# CNEPuckCPURevG.net
KiCad netlist of a schematic drawn in Altium Designer
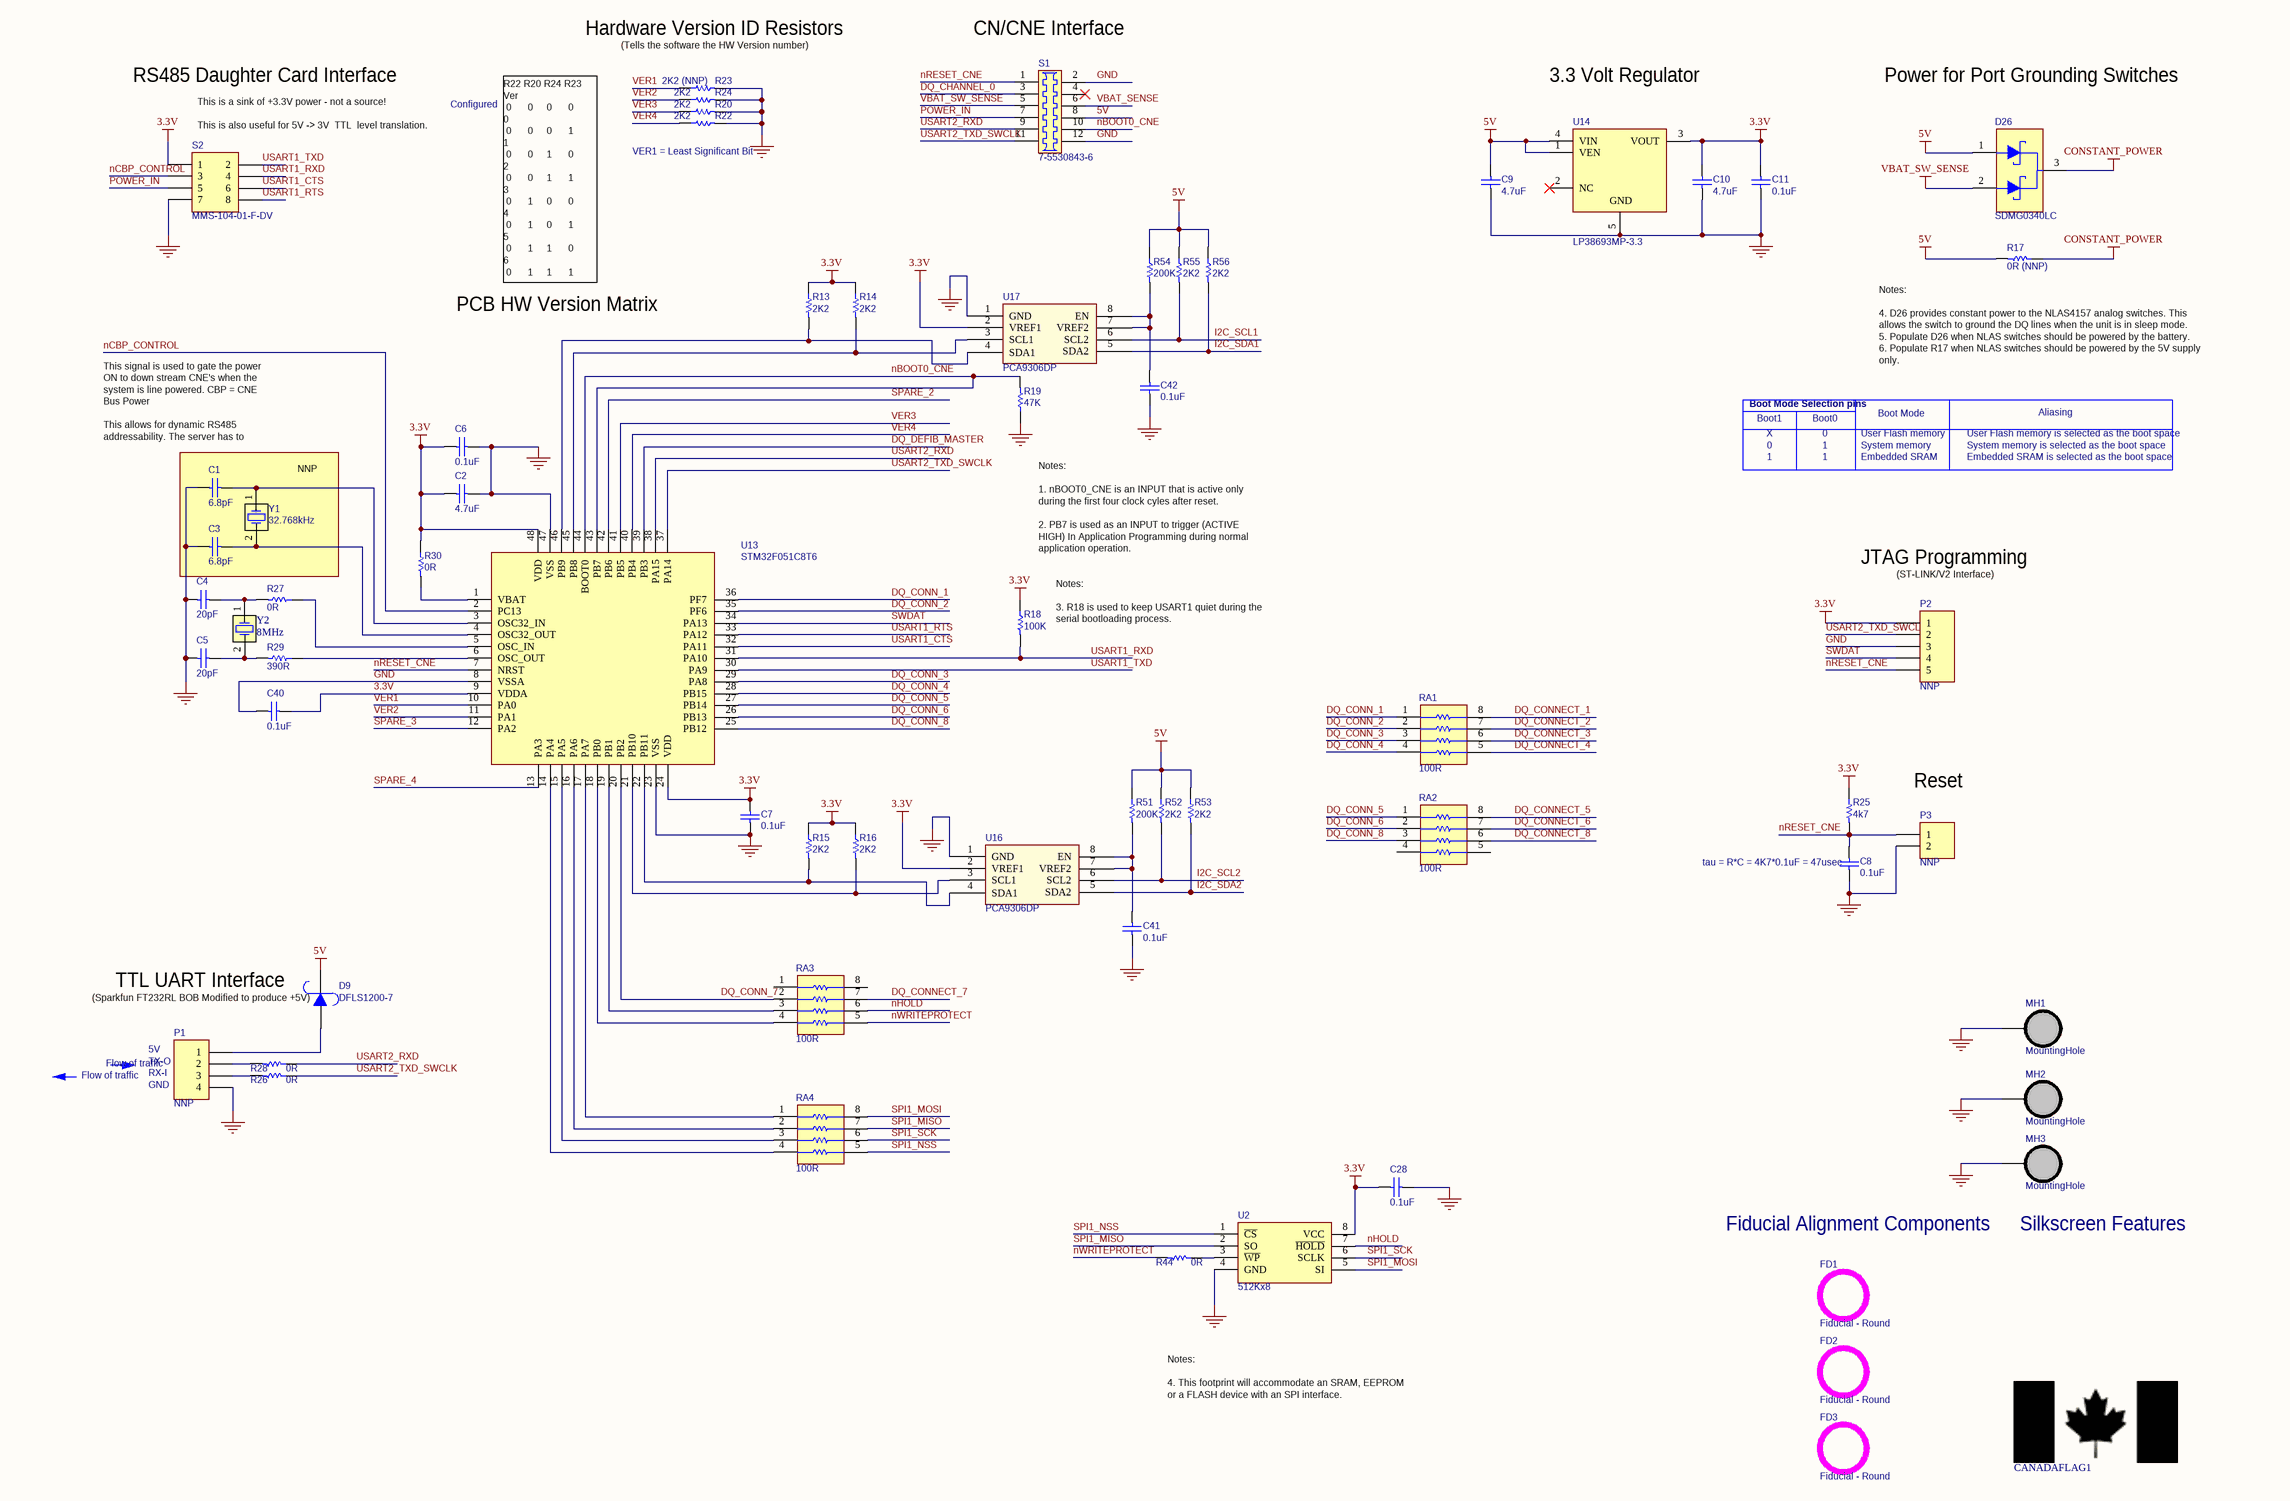
[diagram p0: CNEPuckCPURevG.SchDoc]

(export (version "E")
  (design (tool "Eeschema 10.0.6"))
  (components
    (comp (ref "C1")
      (value "6.8pF")
      (footprint "RC0603")
      (description "CAP CER 6.8PF 50V NP0 0603")
      (fields
        (field (name "MANUFACTURER") "TDK Corporation")
        (field (name "MANUFACTURER PART NUMBER") "C1608C0G1H6R8D")
      )
      (libsource (lib "Swage") (part "C1608C0G1H6R8D"))
    )
    (comp (ref "C2")
      (value "4.7uF")
      (footprint "RC0603")
      (description "CAP CER 4.7UF 10V 10% X5R 0603")
      (fields
        (field (name "MANUFACTURER") "TDK Corporation")
        (field (name "MANUFACTURER PART NUMBER") "C1608X5R1A475K/0.50")
      )
      (libsource (lib "Swage") (part "C1608X5R1A475K/0.50"))
    )
    (comp (ref "C3")
      (value "6.8pF")
      (footprint "RC0603")
      (description "CAP CER 6.8PF 50V NP0 0603")
      (fields
        (field (name "MANUFACTURER") "TDK Corporation")
        (field (name "MANUFACTURER PART NUMBER") "C1608C0G1H6R8D")
      )
      (libsource (lib "Swage") (part "C1608C0G1H6R8D"))
    )
    (comp (ref "C4")
      (value "20pF")
      (footprint "RC0603")
      (description "CAP CER 20PF 50V 5% NPO 0603")
      (fields
        (field (name "MANUFACTURER") "Yageo")
        (field (name "MANUFACTURER PART NUMBER") "CC0603JRNPO9BN200")
      )
      (libsource (lib "Swage") (part "CC0603JRNPO9BN200"))
    )
    (comp (ref "C5")
      (value "20pF")
      (footprint "RC0603")
      (description "CAP CER 20PF 50V 5% NPO 0603")
      (fields
        (field (name "MANUFACTURER") "Yageo")
        (field (name "MANUFACTURER PART NUMBER") "CC0603JRNPO9BN200")
      )
      (libsource (lib "Swage") (part "CC0603JRNPO9BN200"))
    )
    (comp (ref "C6")
      (value "0.1uF")
      (footprint "RC0603")
      (description "CAP CERM .1UF 10% 16V X7R 0603")
      (fields (field (name "TOLERANCE") "±10%") (field (name "MANUFACTURER PART NUMBER") "0603YC104KAT2A"))
      (libsource (lib "Swage") (part "0603YC104KAT2A"))
    )
    (comp (ref "C7")
      (value "0.1uF")
      (footprint "RC0603")
      (description "CAP CERM .1UF 10% 16V X7R 0603")
      (fields (field (name "TOLERANCE") "±10%") (field (name "MANUFACTURER PART NUMBER") "0603YC104KAT2A"))
      (libsource (lib "Swage") (part "0603YC104KAT2A"))
    )
    (comp (ref "C8")
      (value "0.1uF")
      (footprint "RC0603")
      (description "CAP CERM .1UF 10% 16V X7R 0603")
      (fields (field (name "TOLERANCE") "±10%") (field (name "MANUFACTURER PART NUMBER") "0603YC104KAT2A"))
      (libsource (lib "Swage") (part "0603YC104KAT2A"))
    )
    (comp (ref "C9")
      (value "4.7uF")
      (footprint "RC0603")
      (description "CAP CER 4.7UF 10V 10% X5R 0603")
      (fields
        (field (name "MANUFACTURER") "TDK Corporation")
        (field (name "MANUFACTURER PART NUMBER") "C1608X5R1A475K/0.50")
      )
      (libsource (lib "Swage") (part "C1608X5R1A475K/0.50"))
    )
    (comp (ref "C10")
      (value "4.7uF")
      (footprint "RC0603")
      (description "CAP CER 4.7UF 10V 10% X5R 0603")
      (fields
        (field (name "MANUFACTURER") "TDK Corporation")
        (field (name "MANUFACTURER PART NUMBER") "C1608X5R1A475K/0.50")
      )
      (libsource (lib "Swage") (part "C1608X5R1A475K/0.50"))
    )
    (comp (ref "C11")
      (value "0.1uF")
      (footprint "RC0603")
      (description "CAP CERM .1UF 10% 16V X7R 0603")
      (fields (field (name "TOLERANCE") "±10%") (field (name "MANUFACTURER PART NUMBER") "0603YC104KAT2A"))
      (libsource (lib "Swage") (part "0603YC104KAT2A"))
    )
    (comp (ref "C28")
      (value "0.1uF")
      (footprint "RC0603")
      (description "CAP CERM .1UF 10% 16V X7R 0603")
      (fields (field (name "TOLERANCE") "±10%") (field (name "MANUFACTURER PART NUMBER") "0603YC104KAT2A"))
      (libsource (lib "Swage") (part "0603YC104KAT2A"))
    )
    (comp (ref "C40")
      (value "0.1uF")
      (footprint "RC0603")
      (description "CAP CERM .1UF 10% 16V X7R 0603")
      (fields (field (name "TOLERANCE") "±10%") (field (name "MANUFACTURER PART NUMBER") "0603YC104KAT2A"))
      (libsource (lib "Swage") (part "0603YC104KAT2A"))
    )
    (comp (ref "C41")
      (value "0.1uF")
      (footprint "RC0603")
      (description "CAP CERM .1UF 10% 16V X7R 0603")
      (fields (field (name "TOLERANCE") "±10%") (field (name "MANUFACTURER PART NUMBER") "0603YC104KAT2A"))
      (libsource (lib "Swage") (part "0603YC104KAT2A"))
    )
    (comp (ref "C42")
      (value "0.1uF")
      (footprint "RC0603")
      (description "CAP CERM .1UF 10% 16V X7R 0603")
      (fields (field (name "TOLERANCE") "±10%") (field (name "MANUFACTURER PART NUMBER") "0603YC104KAT2A"))
      (libsource (lib "Swage") (part "0603YC104KAT2A"))
    )
    (comp (ref "CANADAFLAG1")
      (value "Canada Flag")
      (footprint "CanadaFlag500x250")
      (libsource (lib "Swage") (part "CanadaFlag"))
    )
    (comp (ref "D9")
      (value "DFLS1200-7")
      (footprint "POWERDI-123")
      (description "DIODE SCHOTTKY 1A 200V PWRDI 123")
      (fields (field (name "MANUFACTURER") "Diodes Inc"))
      (libsource (lib "Swage") (part "DFLS1200-7"))
    )
    (comp (ref "D26")
      (value "SDMG0340LC")
      (footprint "SOT-323")
      (description "DIODE SCHOTTKY 40V 30MA SOT323")
      (fields
        (field (name "MANUFACTURER") "Diodes Inc")
        (field (name "MANUFACTURER PART NUMBER") "SDMG0340LC-7-F")
      )
      (libsource (lib "Swage") (part "SDMG0340LC-7-F"))
    )
    (comp (ref "FD1")
      (value "Fiducial - Round")
      (footprint "FIDUCIAL ROUND SMALL")
      (description "Fiducial Round")
      (libsource (lib "StormaxV13") (part "Fiducial"))
    )
    (comp (ref "FD2")
      (value "Fiducial - Round")
      (footprint "FIDUCIAL ROUND SMALL")
      (description "Fiducial Round")
      (libsource (lib "StormaxV13") (part "Fiducial"))
    )
    (comp (ref "FD3")
      (value "Fiducial - Round")
      (footprint "FIDUCIAL ROUND SMALL")
      (description "Fiducial Round")
      (libsource (lib "StormaxV13") (part "Fiducial"))
    )
    (comp (ref "MH1")
      (value "MountingHole")
      (footprint "MountingHole")
      (description "PCB Mounting Hole, 0.150\" hole, 0.270\" Keepout")
      (libsource (lib "Swage") (part "MountingHole"))
    )
    (comp (ref "MH2")
      (value "MountingHole")
      (footprint "MountingHole")
      (description "PCB Mounting Hole, 0.150\" hole, 0.270\" Keepout")
      (libsource (lib "Swage") (part "MountingHole"))
    )
    (comp (ref "MH3")
      (value "MountingHole")
      (footprint "MountingHole")
      (description "PCB Mounting Hole, 0.150\" hole, 0.270\" Keepout")
      (libsource (lib "Swage") (part "MountingHole"))
    )
    (comp (ref "P1")
      (value "NNP")
      (footprint "HDR1X4")
      (description "Header, 4-Pin")
      (fields
        (field (name "MANUFACTURER") "3M")
        (field (name "MANUFACTURER PART NUMBER") "2340-6111TG")
        (field (name "PUBLISHER") "Altium Limited")
      )
      (libsource (lib "Swage") (part "Header 4"))
    )
    (comp (ref "P2")
      (value "NNP")
      (footprint "HDR1X5")
      (description "Header, 5-Pin")
      (fields
        (field (name "MANUFACTURER PART NUMBER") "2340-6111TG")
        (field (name "MANUFACTURER") "3M")
        (field (name "PUBLISHER") "Altium Limited")
      )
      (libsource (lib "Miscellaneous Connectors") (part "Header 5"))
    )
    (comp (ref "P3")
      (value "NNP")
      (footprint "HDR1X2")
      (description "Header, 2-Pin")
      (fields
        (field (name "MANUFACTURER") "3M")
        (field (name "MANUFACTURER PART NUMBER") "2340-6111TG")
        (field (name "PUBLISHER") "Altium Limited")
      )
      (libsource (lib "Miscellaneous Connectors") (part "Header 2"))
    )
    (comp (ref "R13")
      (value "2K2")
      (footprint "RC0603")
      (description "RES 2.2K OHM 1/10W 5% 0603 SMD")
      (fields
        (field (name "MANUFACTURER") "Panasonic Electronic Components")
        (field (name "MANUFACTURER PART NUMBER") "ERJ-3GEYJ222V")
      )
      (libsource (lib "Swage") (part "ERJ-3GEYJ222V"))
    )
    (comp (ref "R14")
      (value "2K2")
      (footprint "RC0603")
      (description "RES 2.2K OHM 1/10W 5% 0603 SMD")
      (fields
        (field (name "MANUFACTURER") "Panasonic Electronic Components")
        (field (name "MANUFACTURER PART NUMBER") "ERJ-3GEYJ222V")
      )
      (libsource (lib "Swage") (part "ERJ-3GEYJ222V"))
    )
    (comp (ref "R15")
      (value "2K2")
      (footprint "RC0603")
      (description "RES 2.2K OHM 1/10W 5% 0603 SMD")
      (fields
        (field (name "MANUFACTURER") "Panasonic Electronic Components")
        (field (name "MANUFACTURER PART NUMBER") "ERJ-3GEYJ222V")
      )
      (libsource (lib "Swage") (part "ERJ-3GEYJ222V"))
    )
    (comp (ref "R16")
      (value "2K2")
      (footprint "RC0603")
      (description "RES 2.2K OHM 1/10W 5% 0603 SMD")
      (fields
        (field (name "MANUFACTURER") "Panasonic Electronic Components")
        (field (name "MANUFACTURER PART NUMBER") "ERJ-3GEYJ222V")
      )
      (libsource (lib "Swage") (part "ERJ-3GEYJ222V"))
    )
    (comp (ref "R17")
      (value "0R (NNP)")
      (footprint "RC0603")
      (description "RES 0.0 OHM 1/10W 0603 SMD")
      (fields (field (name "TOLERANCE") "Jumper") (field (name "MANUFACTURER") "Panasonic - ECG"))
      (libsource (lib "Swage") (part "ERJ-3GEY0R00V"))
    )
    (comp (ref "R18")
      (value "100K")
      (footprint "RC0603")
      (description "RES 100K OHM 1/10W 5% 0603 SMD")
      (fields
        (field (name "MANUFACTURER") "Panasonic Electronic Components")
        (field (name "MANUFACTURER PART NUMBER") "ERJ-3GEYJ104V")
      )
      (libsource (lib "Swage") (part "ERJ-3GEYJ104V"))
    )
    (comp (ref "R19")
      (value "47K")
      (footprint "RC0603")
      (description "RES 47K OHM 1/10W 5% 0603 SMD")
      (fields (field (name "TOLERANCE") "±5%") (field (name "MANUFACTURER") "Panasonic - ECG"))
      (libsource (lib "Swage") (part "ERJ-3GEYJ473V"))
    )
    (comp (ref "R20")
      (value "2K2")
      (footprint "RC0603")
      (description "RES 2.2K OHM 1/10W 5% 0603 SMD")
      (fields
        (field (name "MANUFACTURER") "Panasonic Electronic Components")
        (field (name "MANUFACTURER PART NUMBER") "ERJ-3GEYJ222V")
      )
      (libsource (lib "Swage") (part "ERJ-3GEYJ222V"))
    )
    (comp (ref "R22")
      (value "2K2")
      (footprint "RC0603")
      (description "RES 2.2K OHM 1/10W 5% 0603 SMD")
      (fields
        (field (name "MANUFACTURER") "Panasonic Electronic Components")
        (field (name "MANUFACTURER PART NUMBER") "ERJ-3GEYJ222V")
      )
      (libsource (lib "Swage") (part "ERJ-3GEYJ222V"))
    )
    (comp (ref "R23")
      (value "2K2 (NNP)")
      (footprint "RC0603")
      (description "RES 2.2K OHM 1/10W 5% 0603 SMD")
      (fields
        (field (name "MANUFACTURER") "Panasonic Electronic Components")
        (field (name "MANUFACTURER PART NUMBER") "ERJ-3GEYJ222V")
      )
      (libsource (lib "Swage") (part "ERJ-3GEYJ222V"))
    )
    (comp (ref "R24")
      (value "2K2")
      (footprint "RC0603")
      (description "RES 2.2K OHM 1/10W 5% 0603 SMD")
      (fields
        (field (name "MANUFACTURER") "Panasonic Electronic Components")
        (field (name "MANUFACTURER PART NUMBER") "ERJ-3GEYJ222V")
      )
      (libsource (lib "Swage") (part "ERJ-3GEYJ222V"))
    )
    (comp (ref "R25")
      (value "4k7")
      (footprint "RC0603")
      (description "RES 4.7K OHM 1/10W 5% 0603 SMD")
      (fields
        (field (name "MANUFACTURER") "Panasonic - ECG")
        (field (name "MANUFACTURER PART NUMBER") "ERJ-3GEYJ472V")
      )
      (libsource (lib "Swage") (part "ERJ-3GEYJ472V"))
    )
    (comp (ref "R26")
      (value "0R")
      (footprint "RC0603")
      (description "RES 0.0 OHM 1/10W 0603 SMD")
      (fields (field (name "TOLERANCE") "Jumper") (field (name "MANUFACTURER") "Panasonic - ECG"))
      (libsource (lib "Swage") (part "ERJ-3GEY0R00V"))
    )
    (comp (ref "R27")
      (value "0R")
      (footprint "RC0603")
      (description "RES 0.0 OHM 1/10W 0603 SMD")
      (fields (field (name "TOLERANCE") "Jumper") (field (name "MANUFACTURER") "Panasonic - ECG"))
      (libsource (lib "Swage") (part "ERJ-3GEY0R00V"))
    )
    (comp (ref "R28")
      (value "0R")
      (footprint "RC0603")
      (description "RES 0.0 OHM 1/10W 0603 SMD")
      (fields (field (name "TOLERANCE") "Jumper") (field (name "MANUFACTURER") "Panasonic - ECG"))
      (libsource (lib "Swage") (part "ERJ-3GEY0R00V"))
    )
    (comp (ref "R29")
      (value "390R")
      (footprint "RC0603")
      (description "RES 390 OHM 1/10W 5% 0603 SMD")
      (fields
        (field (name "MANUFACTURER") "Panasonic Electronic Components")
        (field (name "MANUFACTURER PART NUMBER") "ERJ-3GEYJ391V")
      )
      (libsource (lib "Swage") (part "ERJ-3GEYJ391V"))
    )
    (comp (ref "R30")
      (value "0R")
      (footprint "RC0603")
      (description "RES 0.0 OHM 1/10W 0603 SMD")
      (fields (field (name "TOLERANCE") "Jumper") (field (name "MANUFACTURER") "Panasonic - ECG"))
      (libsource (lib "Swage") (part "ERJ-3GEY0R00V"))
    )
    (comp (ref "R44")
      (value "0R")
      (footprint "RC0603")
      (description "RES 0.0 OHM 1/10W 0603 SMD")
      (fields (field (name "TOLERANCE") "Jumper") (field (name "MANUFACTURER") "Panasonic - ECG"))
      (libsource (lib "Swage") (part "ERJ-3GEY0R00V"))
    )
    (comp (ref "R51")
      (value "200K")
      (footprint "RC0603")
      (description "RES 200K OHM 1/10W 5% 0603 SMD")
      (fields
        (field (name "MANUFACTURER") "Panasonic Electronic Components")
        (field (name "MANUFACTURER PART NUMBER") "ERJ-3GEYJ204V")
      )
      (libsource (lib "Swage") (part "ERJ-3GEYJ204V"))
    )
    (comp (ref "R52")
      (value "2K2")
      (footprint "RC0603")
      (description "RES 2.2K OHM 1/10W 5% 0603 SMD")
      (fields
        (field (name "MANUFACTURER") "Panasonic Electronic Components")
        (field (name "MANUFACTURER PART NUMBER") "ERJ-3GEYJ222V")
      )
      (libsource (lib "Swage") (part "ERJ-3GEYJ222V"))
    )
    (comp (ref "R53")
      (value "2K2")
      (footprint "RC0603")
      (description "RES 2.2K OHM 1/10W 5% 0603 SMD")
      (fields
        (field (name "MANUFACTURER") "Panasonic Electronic Components")
        (field (name "MANUFACTURER PART NUMBER") "ERJ-3GEYJ222V")
      )
      (libsource (lib "Swage") (part "ERJ-3GEYJ222V"))
    )
    (comp (ref "R54")
      (value "200K")
      (footprint "RC0603")
      (description "RES 200K OHM 1/10W 5% 0603 SMD")
      (fields
        (field (name "MANUFACTURER") "Panasonic Electronic Components")
        (field (name "MANUFACTURER PART NUMBER") "ERJ-3GEYJ204V")
      )
      (libsource (lib "Swage") (part "ERJ-3GEYJ204V"))
    )
    (comp (ref "R55")
      (value "2K2")
      (footprint "RC0603")
      (description "RES 2.2K OHM 1/10W 5% 0603 SMD")
      (fields
        (field (name "MANUFACTURER") "Panasonic Electronic Components")
        (field (name "MANUFACTURER PART NUMBER") "ERJ-3GEYJ222V")
      )
      (libsource (lib "Swage") (part "ERJ-3GEYJ222V"))
    )
    (comp (ref "R56")
      (value "2K2")
      (footprint "RC0603")
      (description "RES 2.2K OHM 1/10W 5% 0603 SMD")
      (fields
        (field (name "MANUFACTURER") "Panasonic Electronic Components")
        (field (name "MANUFACTURER PART NUMBER") "ERJ-3GEYJ222V")
      )
      (libsource (lib "Swage") (part "ERJ-3GEYJ222V"))
    )
    (comp (ref "RA1")
      (value "100R")
      (footprint "exb28v")
      (description "RES ARRAY 100 OHM 4 RES 0804")
      (fields
        (field (name "MANUFACTURER") "Panasonic Electronic Components")
        (field (name "MANUFACTURER PART NUMBER") "EXB-28V101JX")
      )
      (libsource (lib "Swage") (part "EXB-28V101JX"))
    )
    (comp (ref "RA2")
      (value "100R")
      (footprint "exb28v")
      (description "RES ARRAY 100 OHM 4 RES 0804")
      (fields
        (field (name "MANUFACTURER") "Panasonic Electronic Components")
        (field (name "MANUFACTURER PART NUMBER") "EXB-28V101JX")
      )
      (libsource (lib "Swage") (part "EXB-28V101JX"))
    )
    (comp (ref "RA3")
      (value "100R")
      (footprint "exb28v")
      (description "RES ARRAY 100 OHM 4 RES 0804")
      (fields
        (field (name "MANUFACTURER") "Panasonic Electronic Components")
        (field (name "MANUFACTURER PART NUMBER") "EXB-28V101JX")
      )
      (libsource (lib "Swage") (part "EXB-28V101JX"))
    )
    (comp (ref "RA4")
      (value "100R")
      (footprint "exb28v")
      (description "RES ARRAY 100 OHM 4 RES 0804")
      (fields
        (field (name "MANUFACTURER") "Panasonic Electronic Components")
        (field (name "MANUFACTURER PART NUMBER") "EXB-28V101JX")
      )
      (libsource (lib "Swage") (part "EXB-28V101JX"))
    )
    (comp (ref "S1")
      (value "7-5530843-6")
      (footprint "EdgeConnector-6-12")
      (description "CONN EDGECARD 6POS .100 VERT")
      (fields (field (name "MANUFACTURER") "TE Connectivity"))
      (libsource (lib "Swage") (part "7-5530843-6"))
    )
    (comp (ref "S2")
      (value "MMS-104-01-F-DV")
      (footprint "hirose-2x4")
      (description "CONN RCPT 2MM 8POS DL VERT PCB")
      (fields (field (name "MANUFACTURER") "Samtec Inc"))
      (libsource (lib "Swage") (part "MMS-104-01-F-DV"))
    )
    (comp (ref "U2")
      (value "512Kx8")
      (footprint "SOIC127P600X265-8N")
      (description "IC SRAM SPI 512K 2.5V 8SOIC")
      (fields
        (field (name "MANUFACTURER") "Microchip Technology")
        (field (name "MANUFACTURER PART NUMBER") "23LCV512-I/SN")
      )
      (libsource (lib "Swage") (part "23LCV512-I/SN"))
    )
    (comp (ref "U13")
      (value "STM32F051C8T6")
      (footprint "LQFP48-7x7mm")
      (description "IC MCU 32BIT 64KB FLASH 48LQFP")
      (fields (field (name "MANUFACTURER") "STMicroelectronics"))
      (libsource (lib "Swage") (part "STM32F051C8T6"))
    )
    (comp (ref "U14")
      (value "LP38693MP-3.3")
      (footprint "SOT223")
      (description "IC REG LDO 500MA 3.3V SOT223-4")
      (fields
        (field (name "MANUFACTURER") "National Semiconductor")
        (field (name "MANUFACTURER PART NUMBER") "LP38693MP-3.3/NOPB")
      )
      (libsource (lib "Swage") (part "LP38693MP-3.3/NOPB"))
    )
    (comp (ref "U16")
      (value "PCA9306DP")
      (footprint "TSOP65P640X120-8N")
      (description "IC LEVEL TRANSLATOR - TSSOP8")
      (fields
        (field (name "MANUFACTURER") "ON Semiconductor")
        (field (name "MANUFACTURER PART NUMBER") "PCA9306DTR2G")
      )
      (libsource (lib "Swage") (part "PCA9306DP"))
    )
    (comp (ref "U17")
      (value "PCA9306DP")
      (footprint "TSOP65P640X120-8N")
      (description "IC LEVEL TRANSLATOR - TSSOP8")
      (fields
        (field (name "MANUFACTURER") "ON Semiconductor")
        (field (name "MANUFACTURER PART NUMBER") "PCA9306DTR2G")
      )
      (libsource (lib "Swage") (part "PCA9306DP"))
    )
    (comp (ref "Y1")
      (value "32.768kHz")
      (footprint "FX135")
      (description "CRYSTAL 32.768KHZ 12.5PF SMD")
      (fields
        (field (name "MANUFACTURER") "Fox Electronics")
        (field (name "MANUFACTURER PART NUMBER") "FX135A-327")
      )
      (libsource (lib "Swage") (part "FX135A-327"))
    )
    (comp (ref "Y2")
      (value "8MHz")
      (footprint "NX8045GB")
      (description "CRYSTAL 8.000000 MHZ 8PF SMD")
      (fields
        (field (name "MANUFACTURER") "NDK")
        (field (name "MANUFACTURER PART NUMBER") "NX8045GB-8.000000MHZ")
      )
      (libsource (lib "Swage") (part "NX8045GB-8.000000MHZ"))
    )
  )
  (nets
    (net (code "1") (name "/DQ_CHANNEL_0") (class "Default")
      (node (ref "S1") (pin "3") (pinfunction "DESIGNATOR=3_3") (pintype "passive"))
    )
    (net (code "2") (name "/DQ_CONNECT_1") (class "Default")
      (node (ref "RA1") (pin "8") (pinfunction "8_8") (pintype "passive"))
    )
    (net (code "3") (name "/DQ_CONNECT_2") (class "Default")
      (node (ref "RA1") (pin "7") (pinfunction "7_7") (pintype "passive"))
    )
    (net (code "4") (name "/DQ_CONNECT_3") (class "Default")
      (node (ref "RA1") (pin "6") (pinfunction "6_6") (pintype "passive"))
    )
    (net (code "5") (name "/DQ_CONNECT_4") (class "Default")
      (node (ref "RA1") (pin "5") (pinfunction "5_5") (pintype "passive"))
    )
    (net (code "6") (name "/DQ_CONNECT_5") (class "Default")
      (node (ref "RA2") (pin "8") (pinfunction "8_8") (pintype "passive"))
    )
    (net (code "7") (name "/DQ_CONNECT_6") (class "Default")
      (node (ref "RA2") (pin "7") (pinfunction "7_7") (pintype "passive"))
    )
    (net (code "8") (name "/DQ_CONNECT_7") (class "Default")
      (node (ref "RA3") (pin "7") (pinfunction "7_7") (pintype "passive"))
    )
    (net (code "9") (name "/DQ_CONNECT_8") (class "Default")
      (node (ref "RA2") (pin "6") (pinfunction "6_6") (pintype "passive"))
    )
    (net (code "10") (name "/DQ_CONN_1") (class "Default")
      (node (ref "RA1") (pin "1") (pinfunction "1_1") (pintype "passive"))
      (node (ref "U13") (pin "36") (pinfunction "PF7_36") (pintype "passive"))
    )
    (net (code "11") (name "/DQ_CONN_2") (class "Default")
      (node (ref "RA1") (pin "2") (pinfunction "2_2") (pintype "passive"))
      (node (ref "U13") (pin "35") (pinfunction "PF6_35") (pintype "passive"))
    )
    (net (code "12") (name "/DQ_CONN_3") (class "Default")
      (node (ref "RA1") (pin "3") (pinfunction "3_3") (pintype "passive"))
      (node (ref "U13") (pin "29") (pinfunction "PA8_29") (pintype "passive"))
    )
    (net (code "13") (name "/DQ_CONN_4") (class "Default")
      (node (ref "RA1") (pin "4") (pinfunction "4_4") (pintype "passive"))
      (node (ref "U13") (pin "28") (pinfunction "PB15_28") (pintype "passive"))
    )
    (net (code "14") (name "/DQ_CONN_5") (class "Default")
      (node (ref "RA2") (pin "1") (pinfunction "1_1") (pintype "passive"))
      (node (ref "U13") (pin "27") (pinfunction "PB14_27") (pintype "passive"))
    )
    (net (code "15") (name "/DQ_CONN_6") (class "Default")
      (node (ref "RA2") (pin "2") (pinfunction "2_2") (pintype "passive"))
      (node (ref "U13") (pin "26") (pinfunction "PB13_26") (pintype "passive"))
    )
    (net (code "16") (name "/DQ_CONN_7") (class "Default")
      (node (ref "RA3") (pin "2") (pinfunction "2_2") (pintype "passive"))
      (node (ref "U13") (pin "20") (pinfunction "PB2_20") (pintype "passive"))
    )
    (net (code "17") (name "/DQ_CONN_8") (class "Default")
      (node (ref "RA2") (pin "3") (pinfunction "3_3") (pintype "passive"))
      (node (ref "U13") (pin "25") (pinfunction "PB12_25") (pintype "passive"))
    )
    (net (code "18") (name "/DQ_DEFIB_MASTER") (class "Default")
      (node (ref "U13") (pin "39") (pinfunction "PB3_39") (pintype "passive"))
    )
    (net (code "19") (name "/I2C_SCL1") (class "Default")
      (node (ref "R55") (pin "2") (pinfunction "2_2") (pintype "passive"))
      (node (ref "U17") (pin "6") (pinfunction "SCL2_6") (pintype "passive"))
    )
    (net (code "20") (name "/I2C_SCL2") (class "Default")
      (node (ref "R52") (pin "2") (pinfunction "2_2") (pintype "passive"))
      (node (ref "U16") (pin "6") (pinfunction "SCL2_6") (pintype "passive"))
    )
    (net (code "21") (name "/I2C_SDA1") (class "Default")
      (node (ref "R56") (pin "2") (pinfunction "2_2") (pintype "passive"))
      (node (ref "U17") (pin "5") (pinfunction "SDA2_5") (pintype "passive"))
    )
    (net (code "22") (name "/I2C_SDA2") (class "Default")
      (node (ref "R53") (pin "2") (pinfunction "2_2") (pintype "passive"))
      (node (ref "U16") (pin "5") (pinfunction "SDA2_5") (pintype "passive"))
    )
    (net (code "23") (name "/POWER_IN") (class "Default")
      (node (ref "S1") (pin "7") (pinfunction "DESIGNATOR=7_7") (pintype "passive"))
      (node (ref "S2") (pin "5") (pinfunction "5_5") (pintype "passive"))
    )
    (net (code "24") (name "/SPARE_2") (class "Default")
      (node (ref "U13") (pin "42") (pinfunction "PB6_42") (pintype "passive"))
    )
    (net (code "25") (name "/SPARE_3") (class "Default")
      (node (ref "U13") (pin "12") (pinfunction "PA2_12") (pintype "passive"))
    )
    (net (code "26") (name "/SPARE_4") (class "Default")
      (node (ref "U13") (pin "13") (pinfunction "PA3_13") (pintype "passive"))
    )
    (net (code "27") (name "/SPI1_MISO") (class "Default")
      (node (ref "RA4") (pin "7") (pinfunction "7_7") (pintype "passive"))
      (node (ref "U2") (pin "2") (pinfunction "SO_2") (pintype "passive"))
    )
    (net (code "28") (name "/SPI1_MOSI") (class "Default")
      (node (ref "RA4") (pin "8") (pinfunction "8_8") (pintype "passive"))
      (node (ref "U2") (pin "5") (pinfunction "SI_5") (pintype "passive"))
    )
    (net (code "29") (name "/SPI1_NSS") (class "Default")
      (node (ref "RA4") (pin "5") (pinfunction "5_5") (pintype "passive"))
      (node (ref "U2") (pin "1") (pinfunction "~{CS}_1") (pintype "passive"))
    )
    (net (code "30") (name "/SPI1_SCK") (class "Default")
      (node (ref "RA4") (pin "6") (pinfunction "6_6") (pintype "passive"))
      (node (ref "U2") (pin "6") (pinfunction "SCLK_6") (pintype "passive"))
    )
    (net (code "31") (name "/SWDAT") (class "Default")
      (node (ref "P2") (pin "4") (pinfunction "4_4") (pintype "passive"))
      (node (ref "U13") (pin "34") (pinfunction "PA13_34") (pintype "passive"))
    )
    (net (code "32") (name "/USART1_CTS") (class "Default")
      (node (ref "S2") (pin "6") (pinfunction "6_6") (pintype "passive"))
      (node (ref "U13") (pin "32") (pinfunction "PA11_32") (pintype "passive"))
    )
    (net (code "33") (name "/USART1_RTS") (class "Default")
      (node (ref "S2") (pin "8") (pinfunction "8_8") (pintype "passive"))
      (node (ref "U13") (pin "33") (pinfunction "PA12_33") (pintype "passive"))
    )
    (net (code "34") (name "/USART1_RXD") (class "Default")
      (node (ref "R18") (pin "2") (pinfunction "2_2") (pintype "passive"))
      (node (ref "S2") (pin "4") (pinfunction "4_4") (pintype "passive"))
      (node (ref "U13") (pin "31") (pinfunction "PA10_31") (pintype "passive"))
    )
    (net (code "35") (name "/USART1_TXD") (class "Default")
      (node (ref "S2") (pin "2") (pinfunction "2_2") (pintype "passive"))
      (node (ref "U13") (pin "30") (pinfunction "PA9_30") (pintype "passive"))
    )
    (net (code "36") (name "/USART2_RXD") (class "Default")
      (node (ref "R28") (pin "2") (pinfunction "2_2") (pintype "passive"))
      (node (ref "S1") (pin "9") (pinfunction "DESIGNATOR=9_9") (pintype "passive"))
      (node (ref "U13") (pin "38") (pinfunction "PA15_38") (pintype "passive"))
    )
    (net (code "37") (name "/USART2_TXD_SWCLK") (class "Default")
      (node (ref "P2") (pin "2") (pinfunction "2_2") (pintype "passive"))
      (node (ref "R26") (pin "2") (pinfunction "2_2") (pintype "passive"))
      (node (ref "S1") (pin "11") (pinfunction "DESIGNATOR=11_11") (pintype "passive"))
      (node (ref "U13") (pin "37") (pinfunction "PA14_37") (pintype "passive"))
    )
    (net (code "38") (name "/VBAT_SENSE") (class "Default")
      (node (ref "S1") (pin "6") (pinfunction "DESIGNATOR=6_6") (pintype "passive"))
    )
    (net (code "39") (name "/VER1") (class "Default")
      (node (ref "R23") (pin "1") (pinfunction "1_1") (pintype "passive"))
      (node (ref "U13") (pin "10") (pinfunction "PA0_10") (pintype "passive"))
    )
    (net (code "40") (name "/VER2") (class "Default")
      (node (ref "R24") (pin "1") (pinfunction "1_1") (pintype "passive"))
      (node (ref "U13") (pin "11") (pinfunction "PA1_11") (pintype "passive"))
    )
    (net (code "41") (name "/VER3") (class "Default")
      (node (ref "R20") (pin "1") (pinfunction "1_1") (pintype "passive"))
      (node (ref "U13") (pin "41") (pinfunction "PB5_41") (pintype "passive"))
    )
    (net (code "42") (name "/VER4") (class "Default")
      (node (ref "R22") (pin "1") (pinfunction "1_1") (pintype "passive"))
      (node (ref "U13") (pin "40") (pinfunction "PB4_40") (pintype "passive"))
    )
    (net (code "43") (name "/nBOOT0_CNE") (class "Default")
      (node (ref "R19") (pin "2") (pinfunction "2_2") (pintype "passive"))
      (node (ref "S1") (pin "10") (pinfunction "DESIGNATOR=10_10") (pintype "passive"))
      (node (ref "U13") (pin "43") (pinfunction "PB7_43") (pintype "passive"))
      (node (ref "U13") (pin "44") (pinfunction "BOOT0_44") (pintype "passive"))
    )
    (net (code "44") (name "/nCBP_CONTROL") (class "Default")
      (node (ref "S2") (pin "3") (pinfunction "3_3") (pintype "passive"))
      (node (ref "U13") (pin "2") (pinfunction "PC13_2") (pintype "passive"))
    )
    (net (code "45") (name "/nHOLD") (class "Default")
      (node (ref "RA3") (pin "6") (pinfunction "6_6") (pintype "passive"))
      (node (ref "U2") (pin "7") (pinfunction "~{HOLD}_7") (pintype "passive"))
    )
    (net (code "46") (name "/nRESET_CNE") (class "Default")
      (node (ref "C8") (pin "2") (pinfunction "2_2") (pintype "passive"))
      (node (ref "P2") (pin "5") (pinfunction "5_5") (pintype "passive"))
      (node (ref "P3") (pin "1") (pinfunction "1_1") (pintype "passive"))
      (node (ref "R25") (pin "2") (pinfunction "2_2") (pintype "passive"))
      (node (ref "S1") (pin "1") (pinfunction "DESIGNATOR=1_1") (pintype "passive"))
      (node (ref "U13") (pin "7") (pinfunction "NRST_7") (pintype "passive"))
    )
    (net (code "47") (name "/nWRITEPROTECT") (class "Default")
      (node (ref "R44") (pin "1") (pinfunction "1_1") (pintype "passive"))
      (node (ref "RA3") (pin "5") (pinfunction "5_5") (pintype "passive"))
    )
    (net (code "48") (name "3.3V") (class "Default")
      (node (ref "C10") (pin "2") (pinfunction "2_2") (pintype "passive"))
      (node (ref "C11") (pin "2") (pinfunction "2_2") (pintype "passive"))
      (node (ref "C2") (pin "2") (pinfunction "2_2") (pintype "passive"))
      (node (ref "C28") (pin "1") (pinfunction "1_1") (pintype "passive"))
      (node (ref "C40") (pin "2") (pinfunction "2_2") (pintype "passive"))
      (node (ref "C6") (pin "1") (pinfunction "1_1") (pintype "passive"))
      (node (ref "C7") (pin "1") (pinfunction "1_1") (pintype "passive"))
      (node (ref "P2") (pin "1") (pinfunction "1_1") (pintype "passive"))
      (node (ref "R13") (pin "1") (pinfunction "1_1") (pintype "passive"))
      (node (ref "R14") (pin "1") (pinfunction "1_1") (pintype "passive"))
      (node (ref "R15") (pin "1") (pinfunction "1_1") (pintype "passive"))
      (node (ref "R16") (pin "1") (pinfunction "1_1") (pintype "passive"))
      (node (ref "R18") (pin "1") (pinfunction "1_1") (pintype "passive"))
      (node (ref "R25") (pin "1") (pinfunction "1_1") (pintype "passive"))
      (node (ref "R30") (pin "2") (pinfunction "2_2") (pintype "passive"))
      (node (ref "S2") (pin "1") (pinfunction "1_1") (pintype "passive"))
      (node (ref "U13") (pin "24") (pinfunction "VDD_24") (pintype "passive"))
      (node (ref "U13") (pin "48") (pinfunction "VDD_48") (pintype "passive"))
      (node (ref "U13") (pin "9") (pinfunction "VDDA_9") (pintype "passive"))
      (node (ref "U14") (pin "3") (pinfunction "VOUT_3") (pintype "passive"))
      (node (ref "U16") (pin "2") (pinfunction "VREF1_2") (pintype "passive"))
      (node (ref "U17") (pin "2") (pinfunction "VREF1_2") (pintype "passive"))
      (node (ref "U2") (pin "8") (pinfunction "VCC_8") (pintype "passive"))
    )
    (net (code "49") (name "5V") (class "Default")
      (node (ref "C9") (pin "2") (pinfunction "2_2") (pintype "passive"))
      (node (ref "D26") (pin "1") (pinfunction "A_1") (pintype "passive"))
      (node (ref "D9") (pin "2") (pinfunction "K_2") (pintype "passive"))
      (node (ref "R17") (pin "1") (pinfunction "1_1") (pintype "passive"))
      (node (ref "R51") (pin "1") (pinfunction "1_1") (pintype "passive"))
      (node (ref "R52") (pin "1") (pinfunction "1_1") (pintype "passive"))
      (node (ref "R53") (pin "1") (pinfunction "1_1") (pintype "passive"))
      (node (ref "R54") (pin "1") (pinfunction "1_1") (pintype "passive"))
      (node (ref "R55") (pin "1") (pinfunction "1_1") (pintype "passive"))
      (node (ref "R56") (pin "1") (pinfunction "1_1") (pintype "passive"))
      (node (ref "S1") (pin "8") (pinfunction "DESIGNATOR=8_8") (pintype "passive"))
      (node (ref "U14") (pin "1") (pinfunction "VEN_1") (pintype "passive"))
      (node (ref "U14") (pin "4") (pinfunction "VIN_4") (pintype "passive"))
    )
    (net (code "50") (name "CONSTANT_POWER") (class "Default")
      (node (ref "D26") (pin "3") (pinfunction "K_3") (pintype "passive"))
      (node (ref "R17") (pin "2") (pinfunction "2_2") (pintype "passive"))
    )
    (net (code "51") (name "GND") (class "Default")
      (node (ref "C1") (pin "2") (pinfunction "2_2") (pintype "passive"))
      (node (ref "C10") (pin "1") (pinfunction "1_1") (pintype "passive"))
      (node (ref "C11") (pin "1") (pinfunction "1_1") (pintype "passive"))
      (node (ref "C2") (pin "1") (pinfunction "1_1") (pintype "passive"))
      (node (ref "C28") (pin "2") (pinfunction "2_2") (pintype "passive"))
      (node (ref "C3") (pin "2") (pinfunction "2_2") (pintype "passive"))
      (node (ref "C4") (pin "1") (pinfunction "1_1") (pintype "passive"))
      (node (ref "C40") (pin "1") (pinfunction "1_1") (pintype "passive"))
      (node (ref "C41") (pin "2") (pinfunction "2_2") (pintype "passive"))
      (node (ref "C42") (pin "2") (pinfunction "2_2") (pintype "passive"))
      (node (ref "C5") (pin "1") (pinfunction "1_1") (pintype "passive"))
      (node (ref "C6") (pin "2") (pinfunction "2_2") (pintype "passive"))
      (node (ref "C7") (pin "2") (pinfunction "2_2") (pintype "passive"))
      (node (ref "C8") (pin "1") (pinfunction "1_1") (pintype "passive"))
      (node (ref "C9") (pin "1") (pinfunction "1_1") (pintype "passive"))
      (node (ref "MH1") (pin "1") (pinfunction "1_1") (pintype "passive"))
      (node (ref "MH2") (pin "1") (pinfunction "1_1") (pintype "passive"))
      (node (ref "MH3") (pin "1") (pinfunction "1_1") (pintype "passive"))
      (node (ref "P1") (pin "4") (pinfunction "4_4") (pintype "passive"))
      (node (ref "P2") (pin "3") (pinfunction "3_3") (pintype "passive"))
      (node (ref "P3") (pin "2") (pinfunction "2_2") (pintype "passive"))
      (node (ref "R19") (pin "1") (pinfunction "1_1") (pintype "passive"))
      (node (ref "R20") (pin "2") (pinfunction "2_2") (pintype "passive"))
      (node (ref "R22") (pin "2") (pinfunction "2_2") (pintype "passive"))
      (node (ref "R23") (pin "2") (pinfunction "2_2") (pintype "passive"))
      (node (ref "R24") (pin "2") (pinfunction "2_2") (pintype "passive"))
      (node (ref "S1") (pin "12") (pinfunction "DESIGNATOR=12_12") (pintype "passive"))
      (node (ref "S1") (pin "2") (pinfunction "DESIGNATOR=2_2") (pintype "passive"))
      (node (ref "S2") (pin "7") (pinfunction "7_7") (pintype "passive"))
      (node (ref "U13") (pin "23") (pinfunction "VSS_23") (pintype "passive"))
      (node (ref "U13") (pin "47") (pinfunction "VSS_47") (pintype "passive"))
      (node (ref "U13") (pin "8") (pinfunction "VSSA_8") (pintype "passive"))
      (node (ref "U14") (pin "5") (pinfunction "GND_5") (pintype "passive"))
      (node (ref "U16") (pin "1") (pinfunction "GND_1") (pintype "passive"))
      (node (ref "U17") (pin "1") (pinfunction "GND_1") (pintype "passive"))
      (node (ref "U2") (pin "4") (pinfunction "GND_4") (pintype "passive"))
    )
    (net (code "52") (name "Net-(D9-A)") (class "Default")
      (node (ref "D9") (pin "1") (pinfunction "A_1") (pintype "passive"))
      (node (ref "P1") (pin "1") (pinfunction "1_1") (pintype "passive"))
    )
    (net (code "53") (name "Net-(P1-Pad2)") (class "Default")
      (node (ref "P1") (pin "2") (pinfunction "2_2") (pintype "passive"))
      (node (ref "R28") (pin "1") (pinfunction "1_1") (pintype "passive"))
    )
    (net (code "54") (name "Net-(P1-Pad3)") (class "Default")
      (node (ref "P1") (pin "3") (pinfunction "3_3") (pintype "passive"))
      (node (ref "R26") (pin "1") (pinfunction "1_1") (pintype "passive"))
    )
    (net (code "55") (name "Net-(U2-~{WP})") (class "Default")
      (node (ref "R44") (pin "2") (pinfunction "2_2") (pintype "passive"))
      (node (ref "U2") (pin "3") (pinfunction "~{WP}_3") (pintype "passive"))
    )
    (net (code "56") (name "Net-(U13-OSC32_IN)") (class "Default")
      (node (ref "C1") (pin "1") (pinfunction "1_1") (pintype "passive"))
      (node (ref "U13") (pin "3") (pinfunction "OSC32_IN_3") (pintype "passive"))
      (node (ref "Y1") (pin "1") (pinfunction "OSC1_1") (pintype "passive"))
    )
    (net (code "57") (name "Net-(U13-OSC32_OUT)") (class "Default")
      (node (ref "C3") (pin "1") (pinfunction "1_1") (pintype "passive"))
      (node (ref "U13") (pin "4") (pinfunction "OSC32_OUT_4") (pintype "passive"))
      (node (ref "Y1") (pin "2") (pinfunction "OSC2_2") (pintype "passive"))
    )
    (net (code "58") (name "Net-(U13-OSC_IN)") (class "Default")
      (node (ref "R27") (pin "2") (pinfunction "2_2") (pintype "passive"))
      (node (ref "U13") (pin "5") (pinfunction "OSC_IN_5") (pintype "passive"))
    )
    (net (code "59") (name "Net-(U13-OSC_OUT)") (class "Default")
      (node (ref "R29") (pin "1") (pinfunction "1_1") (pintype "passive"))
      (node (ref "U13") (pin "6") (pinfunction "OSC_OUT_6") (pintype "passive"))
    )
    (net (code "60") (name "Net-(U13-PA4)") (class "Default")
      (node (ref "RA4") (pin "4") (pinfunction "4_4") (pintype "passive"))
      (node (ref "U13") (pin "14") (pinfunction "PA4_14") (pintype "passive"))
    )
    (net (code "61") (name "Net-(U13-PA5)") (class "Default")
      (node (ref "RA4") (pin "3") (pinfunction "3_3") (pintype "passive"))
      (node (ref "U13") (pin "15") (pinfunction "PA5_15") (pintype "passive"))
    )
    (net (code "62") (name "Net-(U13-PA6)") (class "Default")
      (node (ref "RA4") (pin "2") (pinfunction "2_2") (pintype "passive"))
      (node (ref "U13") (pin "16") (pinfunction "PA6_16") (pintype "passive"))
    )
    (net (code "63") (name "Net-(U13-PA7)") (class "Default")
      (node (ref "RA4") (pin "1") (pinfunction "1_1") (pintype "passive"))
      (node (ref "U13") (pin "17") (pinfunction "PA7_17") (pintype "passive"))
    )
    (net (code "64") (name "Net-(U13-PB0)") (class "Default")
      (node (ref "RA3") (pin "4") (pinfunction "4_4") (pintype "passive"))
      (node (ref "U13") (pin "18") (pinfunction "PB0_18") (pintype "passive"))
    )
    (net (code "65") (name "Net-(U13-PB1)") (class "Default")
      (node (ref "RA3") (pin "3") (pinfunction "3_3") (pintype "passive"))
      (node (ref "U13") (pin "19") (pinfunction "PB1_19") (pintype "passive"))
    )
    (net (code "66") (name "Net-(U13-PB8)") (class "Default")
      (node (ref "R14") (pin "2") (pinfunction "2_2") (pintype "passive"))
      (node (ref "U13") (pin "45") (pinfunction "PB8_45") (pintype "passive"))
      (node (ref "U17") (pin "3") (pinfunction "SCL1_3") (pintype "passive"))
    )
    (net (code "67") (name "Net-(U13-PB9)") (class "Default")
      (node (ref "R13") (pin "2") (pinfunction "2_2") (pintype "passive"))
      (node (ref "U13") (pin "46") (pinfunction "PB9_46") (pintype "passive"))
      (node (ref "U17") (pin "4") (pinfunction "SDA1_4") (pintype "passive"))
    )
    (net (code "68") (name "Net-(U13-PB10)") (class "Default")
      (node (ref "R16") (pin "2") (pinfunction "2_2") (pintype "passive"))
      (node (ref "U13") (pin "21") (pinfunction "PB10_21") (pintype "passive"))
      (node (ref "U16") (pin "3") (pinfunction "SCL1_3") (pintype "passive"))
    )
    (net (code "69") (name "Net-(U13-PB11)") (class "Default")
      (node (ref "R15") (pin "2") (pinfunction "2_2") (pintype "passive"))
      (node (ref "U13") (pin "22") (pinfunction "PB11_22") (pintype "passive"))
      (node (ref "U16") (pin "4") (pinfunction "SDA1_4") (pintype "passive"))
    )
    (net (code "70") (name "Net-(U13-VBAT)") (class "Default")
      (node (ref "R30") (pin "1") (pinfunction "1_1") (pintype "passive"))
      (node (ref "U13") (pin "1") (pinfunction "VBAT_1") (pintype "passive"))
    )
    (net (code "71") (name "Net-(U16-EN)") (class "Default")
      (node (ref "C41") (pin "1") (pinfunction "1_1") (pintype "passive"))
      (node (ref "R51") (pin "2") (pinfunction "2_2") (pintype "passive"))
      (node (ref "U16") (pin "7") (pinfunction "VREF2_7") (pintype "passive"))
      (node (ref "U16") (pin "8") (pinfunction "EN_8") (pintype "passive"))
    )
    (net (code "72") (name "Net-(U17-EN)") (class "Default")
      (node (ref "C42") (pin "1") (pinfunction "1_1") (pintype "passive"))
      (node (ref "R54") (pin "2") (pinfunction "2_2") (pintype "passive"))
      (node (ref "U17") (pin "7") (pinfunction "VREF2_7") (pintype "passive"))
      (node (ref "U17") (pin "8") (pinfunction "EN_8") (pintype "passive"))
    )
    (net (code "73") (name "Net-(Y2-OSC1)") (class "Default")
      (node (ref "C4") (pin "2") (pinfunction "2_2") (pintype "passive"))
      (node (ref "R27") (pin "1") (pinfunction "1_1") (pintype "passive"))
      (node (ref "Y2") (pin "1") (pinfunction "OSC1_1") (pintype "passive"))
    )
    (net (code "74") (name "Net-(Y2-OSC2)") (class "Default")
      (node (ref "C5") (pin "2") (pinfunction "2_2") (pintype "passive"))
      (node (ref "R29") (pin "2") (pinfunction "2_2") (pintype "passive"))
      (node (ref "Y2") (pin "2") (pinfunction "OSC2_2") (pintype "passive"))
    )
    (net (code "75") (name "VBAT_SW_SENSE") (class "Default")
      (node (ref "D26") (pin "2") (pinfunction "A_2") (pintype "passive"))
      (node (ref "S1") (pin "5") (pinfunction "DESIGNATOR=5_5") (pintype "passive"))
    )
    (net (code "76") (name "unconnected-(RA2-Pad4)") (class "Default")
      (node (ref "RA2") (pin "4") (pinfunction "4_4") (pintype "passive"))
    )
    (net (code "77") (name "unconnected-(RA2-Pad5)") (class "Default")
      (node (ref "RA2") (pin "5") (pinfunction "5_5") (pintype "passive"))
    )
    (net (code "78") (name "unconnected-(RA3-Pad1)") (class "Default")
      (node (ref "RA3") (pin "1") (pinfunction "1_1") (pintype "passive"))
    )
    (net (code "79") (name "unconnected-(RA3-Pad8)") (class "Default")
      (node (ref "RA3") (pin "8") (pinfunction "8_8") (pintype "passive"))
    )
    (net (code "80") (name "unconnected-(S1-DESIGNATOR=4-Pad4)") (class "Default")
      (node (ref "S1") (pin "4") (pinfunction "DESIGNATOR=4_4") (pintype "passive+no_connect"))
    )
    (net (code "81") (name "unconnected-(U14-NC-Pad2)") (class "Default")
      (node (ref "U14") (pin "2") (pinfunction "NC_2") (pintype "passive+no_connect"))
    )
  )
)
